# Lid_Sensor.net
KiCad netlist of a schematic drawn in Altium Designer
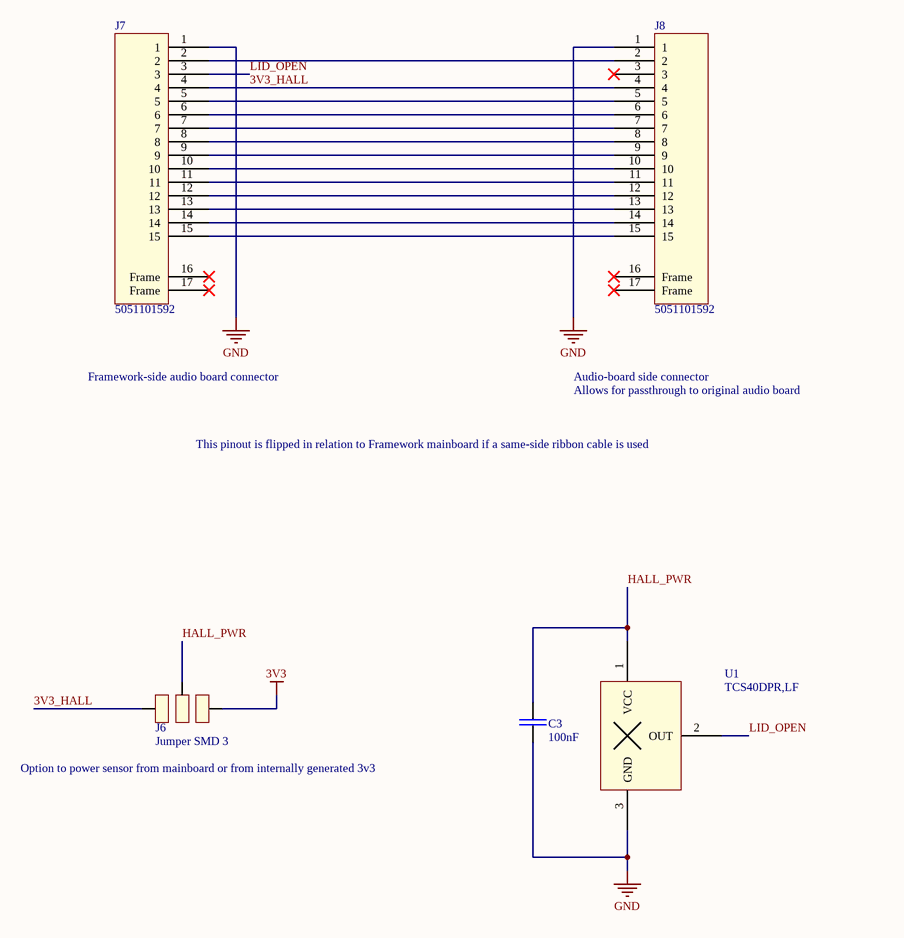
[diagram p0: Lid Sensor.SchDoc]

(export (version "E")
  (design (tool "Eeschema 10.0.6"))
  (components
    (comp (ref "C3")
      (value "100nF")
      (footprint "CAP_SM0603_YAGEOCC2_N")
      (description "CAP 100nF SM0603 X7R 50V YAGEO CC2")
      (fields
        (field (name "MANUFACTURER") "Yageo")
        (field (name "MANUFACTURER PART NUMBER") "CC0603KRX7R9BB104")
      )
      (libsource (lib "Yageo") (part "CC0603KRX7R9BB104"))
    )
    (comp (ref "J6")
      (value "Jumper SMD 3")
      (footprint "Jumper SMD 3")
      (libsource (lib "KBuchka-IntLib") (part "Jumper SMD 3"))
    )
    (comp (ref "J7") (value "5051101592") (footprint "5051101592") (libsource (lib "") (part "5051101592_1")))
    (comp (ref "J8")
      (value "5051101592")
      (footprint "5051101592")
      (libsource (lib "KBuchka-IntLib") (part "5051101592"))
    )
    (comp (ref "U1")
      (value "TCS40DPR,LF")
      (footprint "TCS40DPR,LF - SOT23127P600-8N")
      (libsource (lib "KBuchka-IntLib") (part "TCS40DPR,LF"))
    )
  )
  (nets
    (net (code "1") (name "/3V3_HALL") (class "Default")
      (node (ref "J6") (pin "3") (pinfunction "3_3") (pintype "passive"))
      (node (ref "J7") (pin "4") (pinfunction "4_4") (pintype "passive"))
      (node (ref "J8") (pin "4") (pinfunction "4_4") (pintype "passive"))
    )
    (net (code "2") (name "/HALL_PWR") (class "Default")
      (node (ref "C3") (pin "2") (pintype "passive"))
      (node (ref "J6") (pin "2") (pinfunction "2_2") (pintype "passive"))
      (node (ref "U1") (pin "1") (pinfunction "VCC_1") (pintype "passive"))
    )
    (net (code "3") (name "/LID_OPEN") (class "Default")
      (node (ref "J7") (pin "3") (pinfunction "3_3") (pintype "passive"))
      (node (ref "U1") (pin "2") (pinfunction "OUT_2") (pintype "passive"))
    )
    (net (code "4") (name "3V3") (class "Default")
      (node (ref "J6") (pin "1") (pinfunction "1_1") (pintype "passive"))
    )
    (net (code "5") (name "GND") (class "Default")
      (node (ref "C3") (pin "1") (pintype "passive"))
      (node (ref "J7") (pin "1") (pinfunction "1_1") (pintype "passive"))
      (node (ref "J8") (pin "1") (pinfunction "1_1") (pintype "passive"))
      (node (ref "U1") (pin "3") (pinfunction "GND_3") (pintype "passive"))
    )
    (net (code "6") (name "Net-(J7-Pad2)") (class "Default")
      (node (ref "J7") (pin "2") (pinfunction "2_2") (pintype "passive"))
      (node (ref "J8") (pin "2") (pinfunction "2_2") (pintype "passive"))
    )
    (net (code "7") (name "Net-(J7-Pad5)") (class "Default")
      (node (ref "J7") (pin "5") (pinfunction "5_5") (pintype "passive"))
      (node (ref "J8") (pin "5") (pinfunction "5_5") (pintype "passive"))
    )
    (net (code "8") (name "Net-(J7-Pad6)") (class "Default")
      (node (ref "J7") (pin "6") (pinfunction "6_6") (pintype "passive"))
      (node (ref "J8") (pin "6") (pinfunction "6_6") (pintype "passive"))
    )
    (net (code "9") (name "Net-(J7-Pad7)") (class "Default")
      (node (ref "J7") (pin "7") (pinfunction "7_7") (pintype "passive"))
      (node (ref "J8") (pin "7") (pinfunction "7_7") (pintype "passive"))
    )
    (net (code "10") (name "Net-(J7-Pad8)") (class "Default")
      (node (ref "J7") (pin "8") (pinfunction "8_8") (pintype "passive"))
      (node (ref "J8") (pin "8") (pinfunction "8_8") (pintype "passive"))
    )
    (net (code "11") (name "Net-(J7-Pad9)") (class "Default")
      (node (ref "J7") (pin "9") (pinfunction "9_9") (pintype "passive"))
      (node (ref "J8") (pin "9") (pinfunction "9_9") (pintype "passive"))
    )
    (net (code "12") (name "Net-(J7-Pad10)") (class "Default")
      (node (ref "J7") (pin "10") (pinfunction "10_10") (pintype "passive"))
      (node (ref "J8") (pin "10") (pinfunction "10_10") (pintype "passive"))
    )
    (net (code "13") (name "Net-(J7-Pad11)") (class "Default")
      (node (ref "J7") (pin "11") (pinfunction "11_11") (pintype "passive"))
      (node (ref "J8") (pin "11") (pinfunction "11_11") (pintype "passive"))
    )
    (net (code "14") (name "Net-(J7-Pad12)") (class "Default")
      (node (ref "J7") (pin "12") (pinfunction "12_12") (pintype "passive"))
      (node (ref "J8") (pin "12") (pinfunction "12_12") (pintype "passive"))
    )
    (net (code "15") (name "Net-(J7-Pad13)") (class "Default")
      (node (ref "J7") (pin "13") (pinfunction "13_13") (pintype "passive"))
      (node (ref "J8") (pin "13") (pinfunction "13_13") (pintype "passive"))
    )
    (net (code "16") (name "Net-(J7-Pad14)") (class "Default")
      (node (ref "J7") (pin "14") (pinfunction "14_14") (pintype "passive"))
      (node (ref "J8") (pin "14") (pinfunction "14_14") (pintype "passive"))
    )
    (net (code "17") (name "Net-(J7-Pad15)") (class "Default")
      (node (ref "J7") (pin "15") (pinfunction "15_15") (pintype "passive"))
      (node (ref "J8") (pin "15") (pinfunction "15_15") (pintype "passive"))
    )
    (net (code "18") (name "unconnected-(J7-Frame-Pad16)") (class "Default")
      (node (ref "J7") (pin "16") (pinfunction "Frame_16") (pintype "passive+no_connect"))
    )
    (net (code "19") (name "unconnected-(J7-Frame-Pad17)") (class "Default")
      (node (ref "J7") (pin "17") (pinfunction "Frame_17") (pintype "passive+no_connect"))
    )
    (net (code "20") (name "unconnected-(J8-Frame-Pad16)") (class "Default")
      (node (ref "J8") (pin "16") (pinfunction "Frame_16") (pintype "passive+no_connect"))
    )
    (net (code "21") (name "unconnected-(J8-Frame-Pad17)") (class "Default")
      (node (ref "J8") (pin "17") (pinfunction "Frame_17") (pintype "passive+no_connect"))
    )
    (net (code "22") (name "unconnected-(J8-Pad3)") (class "Default")
      (node (ref "J8") (pin "3") (pinfunction "3_3") (pintype "passive+no_connect"))
    )
  )
)
